# Schematic.net
KiCad netlist of a schematic drawn in EasyEDA
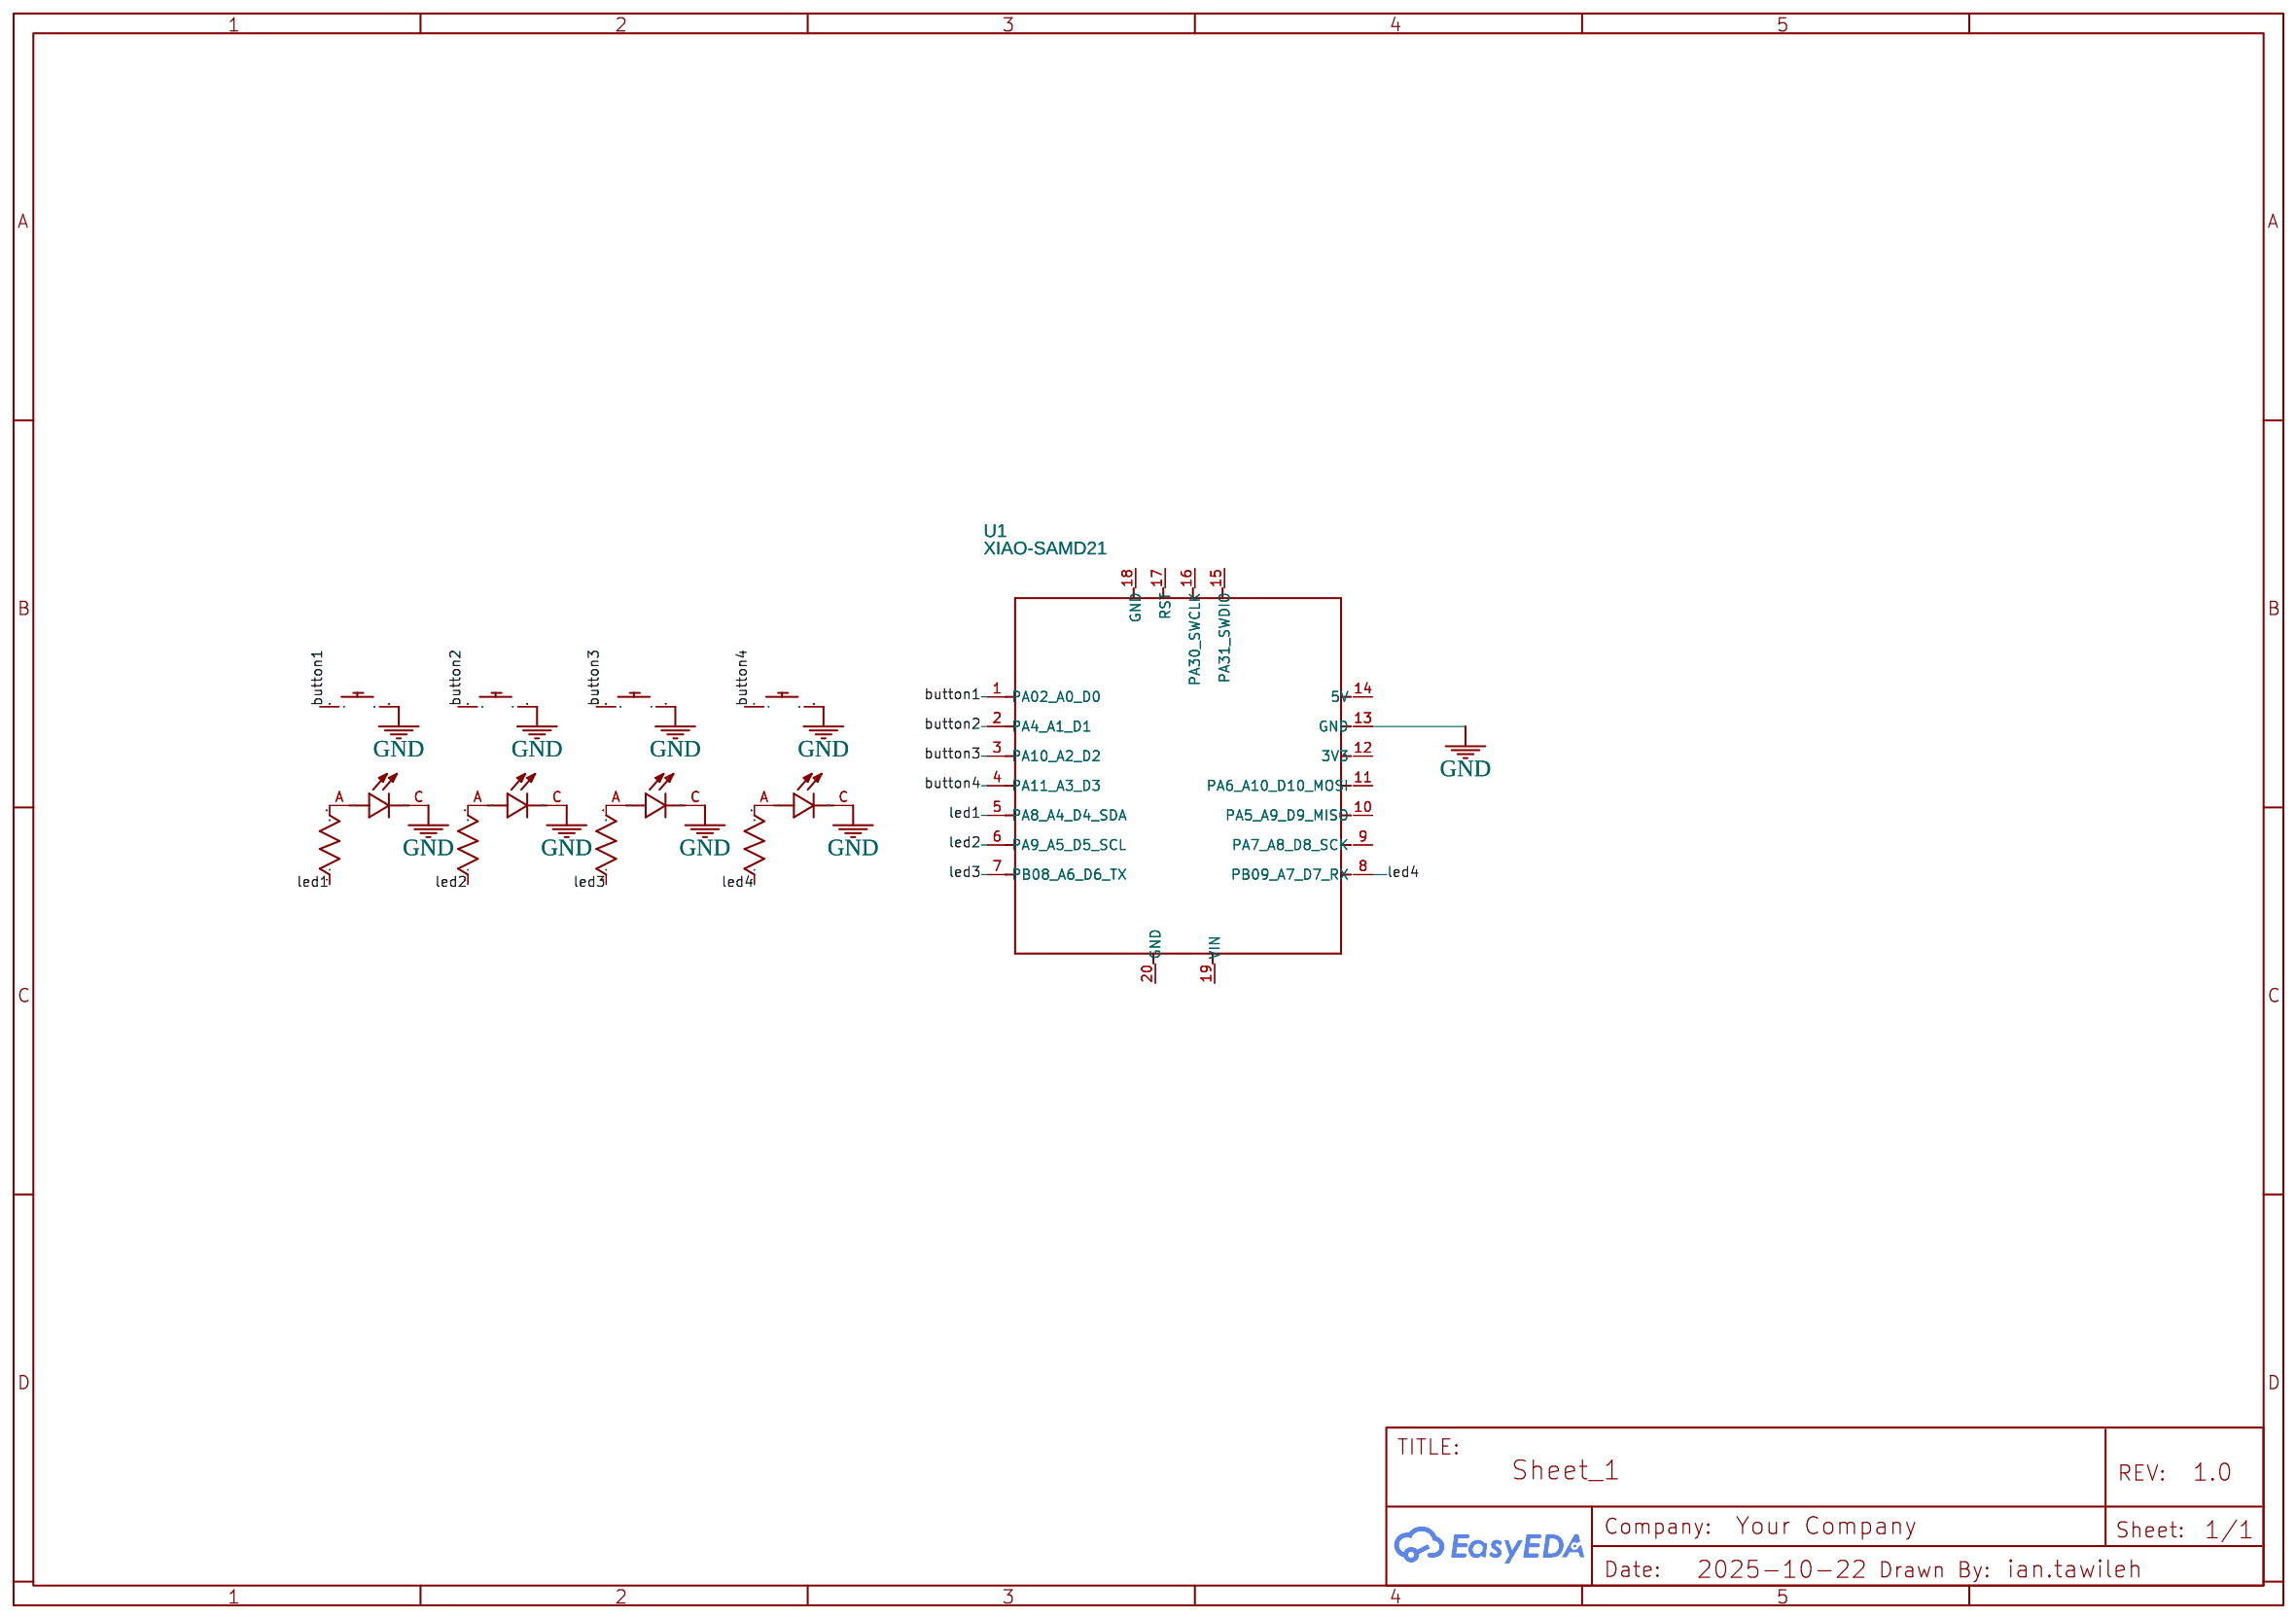
[diagram p0: schematic sheet]

(export (version "E")
  (design (tool "Eeschema 10.0.6"))
  (components
    (comp (ref "D1") (value "L08R5000Q1") (libsource (lib "") (part "L08R5000Q1")))
    (comp (ref "D2") (value "L08R5000Q1") (libsource (lib "") (part "L08R5000Q1")))
    (comp (ref "D3") (value "L08R5000Q1") (libsource (lib "") (part "L08R5000Q1")))
    (comp (ref "D4") (value "L08R5000Q1") (libsource (lib "") (part "L08R5000Q1")))
    (comp (ref "R1") (value "1k") (libsource (lib "") (part "R_0603_US")))
    (comp (ref "R2") (value "1k") (libsource (lib "") (part "R_0603_US")))
    (comp (ref "R3") (value "1k") (libsource (lib "") (part "R_0603_US")))
    (comp (ref "R4") (value "1k") (libsource (lib "") (part "R_0603_US")))
    (comp (ref "S1") (value "CHERRY_CHERRY_MX") (libsource (lib "") (part "CHERRY_CHERRY_MX")))
    (comp (ref "S2") (value "CHERRY_CHERRY_MX") (libsource (lib "") (part "CHERRY_CHERRY_MX")))
    (comp (ref "S3") (value "CHERRY_CHERRY_MX") (libsource (lib "") (part "CHERRY_CHERRY_MX")))
    (comp (ref "S4") (value "CHERRY_CHERRY_MX") (libsource (lib "") (part "CHERRY_CHERRY_MX")))
    (comp (ref "U1") (value "XIAO-SAMD21") (libsource (lib "") (part "XIAO-SAMD21")))
  )
  (nets
    (net (code "1") (name "/button1") (class "Default")
      (node (ref "S1") (pin "1") (pinfunction "1_1") (pintype "bidirectional"))
      (node (ref "U1") (pin "1") (pinfunction "PA02_A0_D0_1") (pintype "bidirectional"))
    )
    (net (code "2") (name "/button2") (class "Default")
      (node (ref "S2") (pin "1") (pinfunction "1_1") (pintype "bidirectional"))
      (node (ref "U1") (pin "2") (pinfunction "PA4_A1_D1_2") (pintype "bidirectional"))
    )
    (net (code "3") (name "/button3") (class "Default")
      (node (ref "S3") (pin "1") (pinfunction "1_1") (pintype "bidirectional"))
      (node (ref "U1") (pin "3") (pinfunction "PA10_A2_D2_3") (pintype "bidirectional"))
    )
    (net (code "4") (name "/button4") (class "Default")
      (node (ref "S4") (pin "1") (pinfunction "1_1") (pintype "bidirectional"))
      (node (ref "U1") (pin "4") (pinfunction "PA11_A3_D3_4") (pintype "bidirectional"))
    )
    (net (code "5") (name "/led1") (class "Default")
      (node (ref "R1") (pin "1") (pinfunction "1_1") (pintype "unspecified"))
      (node (ref "U1") (pin "5") (pinfunction "PA8_A4_D4_SDA_5") (pintype "bidirectional"))
    )
    (net (code "6") (name "/led2") (class "Default")
      (node (ref "R2") (pin "1") (pinfunction "1_1") (pintype "unspecified"))
      (node (ref "U1") (pin "6") (pinfunction "PA9_A5_D5_SCL_6") (pintype "bidirectional"))
    )
    (net (code "7") (name "/led3") (class "Default")
      (node (ref "R3") (pin "1") (pinfunction "1_1") (pintype "unspecified"))
      (node (ref "U1") (pin "7") (pinfunction "PB08_A6_D6_TX_7") (pintype "bidirectional"))
    )
    (net (code "8") (name "/led4") (class "Default")
      (node (ref "R4") (pin "1") (pinfunction "1_1") (pintype "unspecified"))
      (node (ref "U1") (pin "8") (pinfunction "PB09_A7_D7_RX_8") (pintype "bidirectional"))
    )
    (net (code "9") (name "GND") (class "Default")
      (node (ref "D1") (pin "C") (pinfunction "C_C") (pintype "bidirectional"))
      (node (ref "D2") (pin "C") (pinfunction "C_C") (pintype "bidirectional"))
      (node (ref "D3") (pin "C") (pinfunction "C_C") (pintype "bidirectional"))
      (node (ref "D4") (pin "C") (pinfunction "C_C") (pintype "bidirectional"))
      (node (ref "S1") (pin "2") (pinfunction "2_2") (pintype "bidirectional"))
      (node (ref "S2") (pin "2") (pinfunction "2_2") (pintype "bidirectional"))
      (node (ref "S3") (pin "2") (pinfunction "2_2") (pintype "bidirectional"))
      (node (ref "S4") (pin "2") (pinfunction "2_2") (pintype "bidirectional"))
      (node (ref "U1") (pin "13") (pinfunction "GND_13") (pintype "bidirectional"))
    )
    (net (code "10") (name "Net-(D1-PadA)") (class "Default")
      (node (ref "D1") (pin "A") (pinfunction "A_A") (pintype "bidirectional"))
      (node (ref "R1") (pin "2") (pinfunction "2_2") (pintype "unspecified"))
    )
    (net (code "11") (name "Net-(D2-PadA)") (class "Default")
      (node (ref "D2") (pin "A") (pinfunction "A_A") (pintype "bidirectional"))
      (node (ref "R2") (pin "2") (pinfunction "2_2") (pintype "unspecified"))
    )
    (net (code "12") (name "Net-(D3-PadA)") (class "Default")
      (node (ref "D3") (pin "A") (pinfunction "A_A") (pintype "bidirectional"))
      (node (ref "R3") (pin "2") (pinfunction "2_2") (pintype "unspecified"))
    )
    (net (code "13") (name "Net-(D4-PadA)") (class "Default")
      (node (ref "D4") (pin "A") (pinfunction "A_A") (pintype "bidirectional"))
      (node (ref "R4") (pin "2") (pinfunction "2_2") (pintype "unspecified"))
    )
    (net (code "14") (name "unconnected-(U1-3V3-Pad12)") (class "Default")
      (node (ref "U1") (pin "12") (pinfunction "3V3_12") (pintype "bidirectional"))
    )
    (net (code "15") (name "unconnected-(U1-5V-Pad14)") (class "Default")
      (node (ref "U1") (pin "14") (pinfunction "5V_14") (pintype "bidirectional"))
    )
    (net (code "16") (name "unconnected-(U1-GND-Pad18)") (class "Default")
      (node (ref "U1") (pin "18") (pinfunction "GND_18") (pintype "bidirectional"))
    )
    (net (code "17") (name "unconnected-(U1-GND-Pad20)") (class "Default")
      (node (ref "U1") (pin "20") (pinfunction "GND_20") (pintype "bidirectional"))
    )
    (net (code "18") (name "unconnected-(U1-PA5_A9_D9_MISO-Pad10)") (class "Default")
      (node (ref "U1") (pin "10") (pinfunction "PA5_A9_D9_MISO_10") (pintype "bidirectional"))
    )
    (net (code "19") (name "unconnected-(U1-PA6_A10_D10_MOSI-Pad11)") (class "Default")
      (node (ref "U1") (pin "11") (pinfunction "PA6_A10_D10_MOSI_11") (pintype "bidirectional"))
    )
    (net (code "20") (name "unconnected-(U1-PA7_A8_D8_SCK-Pad9)") (class "Default")
      (node (ref "U1") (pin "9") (pinfunction "PA7_A8_D8_SCK_9") (pintype "bidirectional"))
    )
    (net (code "21") (name "unconnected-(U1-PA30_SWCLK-Pad16)") (class "Default")
      (node (ref "U1") (pin "16") (pinfunction "PA30_SWCLK_16") (pintype "bidirectional"))
    )
    (net (code "22") (name "unconnected-(U1-PA31_SWDIO-Pad15)") (class "Default")
      (node (ref "U1") (pin "15") (pinfunction "PA31_SWDIO_15") (pintype "bidirectional"))
    )
    (net (code "23") (name "unconnected-(U1-RST-Pad17)") (class "Default")
      (node (ref "U1") (pin "17") (pinfunction "RST_17") (pintype "bidirectional"))
    )
    (net (code "24") (name "unconnected-(U1-VIN-Pad19)") (class "Default")
      (node (ref "U1") (pin "19") (pinfunction "VIN_19") (pintype "bidirectional"))
    )
  )
)
